# Rejestrator_WD.net
KiCad netlist of a schematic drawn in EAGLE
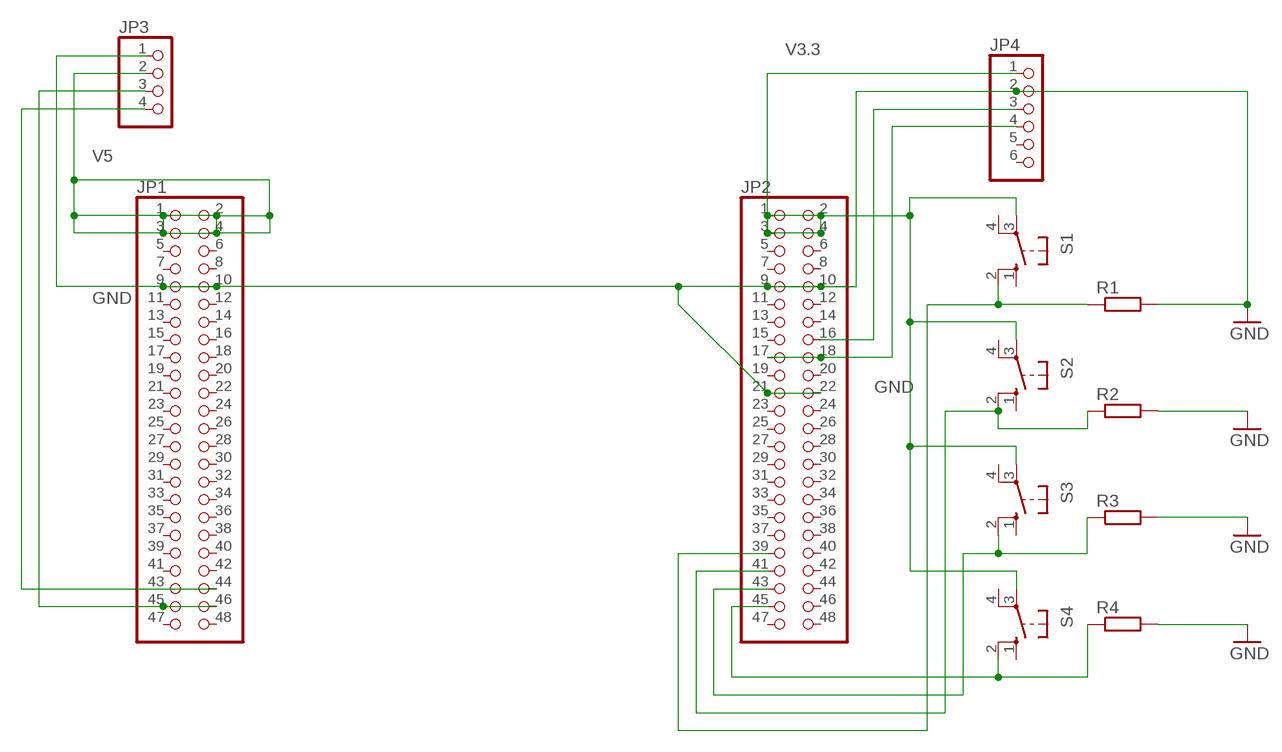
[diagram p0: schematic, sheet 1]

(export (version "E")
  (design (tool "Eeschema 10.0.6"))
  (components
    (comp (ref "JP1")
      (value "PINHD-2X24")
      (footprint "eagle-import:2X24")
      (libsource (lib "eagle-import") (part "PINHD-2X24"))
    )
    (comp (ref "JP2")
      (value "PINHD-2X24")
      (footprint "eagle-import:2X24")
      (libsource (lib "eagle-import") (part "PINHD-2X24"))
    )
    (comp (ref "JP3")
      (value "PINHD-1X4/90")
      (footprint "eagle-import:1X04_90")
      (libsource (lib "eagle-import") (part "PINHD-1X4/90"))
    )
    (comp (ref "JP4")
      (value "PINHD-1X6")
      (footprint "eagle-import:1X06")
      (libsource (lib "eagle-import") (part "PINHD-1X6"))
    )
    (comp (ref "R1")
      (value "R-EU_0207/10")
      (footprint "eagle-import:0207_10")
      (libsource (lib "eagle-import") (part "R-EU_0207/10"))
    )
    (comp (ref "R2")
      (value "R-EU_0207/10")
      (footprint "eagle-import:0207_10")
      (libsource (lib "eagle-import") (part "R-EU_0207/10"))
    )
    (comp (ref "R3")
      (value "R-EU_0207/10")
      (footprint "eagle-import:0207_10")
      (libsource (lib "eagle-import") (part "R-EU_0207/10"))
    )
    (comp (ref "R4")
      (value "R-EU_0207/10")
      (footprint "eagle-import:0207_10")
      (libsource (lib "eagle-import") (part "R-EU_0207/10"))
    )
    (comp (ref "S1")
      (value "40-XX")
      (footprint "eagle-import:B3F-40XX")
      (fields (field (name "MF") "OMRON COMPONENTS USA") (field (name "MPN") "B3F-4000"))
      (libsource (lib "eagle-import") (part "40-XX"))
    )
    (comp (ref "S2")
      (value "40-XX")
      (footprint "eagle-import:B3F-40XX")
      (fields (field (name "MF") "OMRON COMPONENTS USA") (field (name "MPN") "B3F-4000"))
      (libsource (lib "eagle-import") (part "40-XX"))
    )
    (comp (ref "S3")
      (value "40-XX")
      (footprint "eagle-import:B3F-40XX")
      (fields (field (name "MF") "OMRON COMPONENTS USA") (field (name "MPN") "B3F-4000"))
      (libsource (lib "eagle-import") (part "40-XX"))
    )
    (comp (ref "S4")
      (value "40-XX")
      (footprint "eagle-import:B3F-40XX")
      (fields (field (name "MF") "OMRON COMPONENTS USA") (field (name "MPN") "B3F-4000"))
      (libsource (lib "eagle-import") (part "40-XX"))
    )
  )
  (nets
    (net (code "1") (name "/V3.3") (class "Default")
      (node (ref "JP2") (pin "1") (pinfunction "1_1") (pintype "passive"))
      (node (ref "JP2") (pin "2") (pinfunction "2_2") (pintype "passive"))
      (node (ref "JP2") (pin "3") (pinfunction "3_3") (pintype "passive"))
      (node (ref "JP2") (pin "4") (pinfunction "4_4") (pintype "passive"))
      (node (ref "JP4") (pin "1") (pinfunction "1_1") (pintype "passive"))
      (node (ref "S1") (pin "3") (pinfunction "P_3") (pintype "passive"))
      (node (ref "S2") (pin "3") (pinfunction "P_3") (pintype "passive"))
      (node (ref "S3") (pin "3") (pinfunction "P_3") (pintype "passive"))
      (node (ref "S4") (pin "3") (pinfunction "P_3") (pintype "passive"))
    )
    (net (code "2") (name "/V5") (class "Default")
      (node (ref "JP1") (pin "1") (pinfunction "1_1") (pintype "passive"))
      (node (ref "JP1") (pin "2") (pinfunction "2_2") (pintype "passive"))
      (node (ref "JP1") (pin "3") (pinfunction "3_3") (pintype "passive"))
      (node (ref "JP1") (pin "4") (pinfunction "4_4") (pintype "passive"))
      (node (ref "JP3") (pin "2") (pinfunction "2_2") (pintype "passive"))
    )
    (net (code "3") (name "GND") (class "Default")
      (node (ref "JP1") (pin "10") (pinfunction "10_10") (pintype "passive"))
      (node (ref "JP1") (pin "9") (pinfunction "9_9") (pintype "passive"))
      (node (ref "JP2") (pin "10") (pinfunction "10_10") (pintype "passive"))
      (node (ref "JP2") (pin "21") (pinfunction "21_21") (pintype "passive"))
      (node (ref "JP2") (pin "22") (pinfunction "22_22") (pintype "passive"))
      (node (ref "JP2") (pin "9") (pinfunction "9_9") (pintype "passive"))
      (node (ref "JP3") (pin "1") (pinfunction "1_1") (pintype "passive"))
      (node (ref "JP4") (pin "2") (pinfunction "2_2") (pintype "passive"))
      (node (ref "R1") (pin "2") (pinfunction "2_2") (pintype "passive"))
      (node (ref "R2") (pin "2") (pinfunction "2_2") (pintype "passive"))
      (node (ref "R3") (pin "2") (pinfunction "2_2") (pintype "passive"))
      (node (ref "R4") (pin "2") (pinfunction "2_2") (pintype "passive"))
    )
    (net (code "4") (name "Net-(JP1-Pad44)") (class "Default")
      (node (ref "JP1") (pin "44") (pinfunction "44_44") (pintype "passive"))
      (node (ref "JP3") (pin "4") (pinfunction "4_4") (pintype "passive"))
    )
    (net (code "5") (name "Net-(JP1-Pad45)") (class "Default")
      (node (ref "JP1") (pin "45") (pinfunction "45_45") (pintype "passive"))
      (node (ref "JP1") (pin "46") (pinfunction "46_46") (pintype "passive"))
      (node (ref "JP3") (pin "3") (pinfunction "3_3") (pintype "passive"))
    )
    (net (code "6") (name "Net-(JP2-Pad16)") (class "Default")
      (node (ref "JP2") (pin "16") (pinfunction "16_16") (pintype "passive"))
      (node (ref "JP4") (pin "3") (pinfunction "3_3") (pintype "passive"))
    )
    (net (code "7") (name "Net-(JP2-Pad17)") (class "Default")
      (node (ref "JP2") (pin "17") (pinfunction "17_17") (pintype "passive"))
      (node (ref "JP2") (pin "18") (pinfunction "18_18") (pintype "passive"))
      (node (ref "JP4") (pin "4") (pinfunction "4_4") (pintype "passive"))
    )
    (net (code "8") (name "Net-(S1-S1)") (class "Default")
      (node (ref "JP2") (pin "39") (pinfunction "39_39") (pintype "passive"))
      (node (ref "R1") (pin "1") (pinfunction "1_1") (pintype "passive"))
      (node (ref "S1") (pin "2") (pinfunction "S1_2") (pintype "passive"))
    )
    (net (code "9") (name "Net-(S2-S1)") (class "Default")
      (node (ref "JP2") (pin "41") (pinfunction "41_41") (pintype "passive"))
      (node (ref "R2") (pin "1") (pinfunction "1_1") (pintype "passive"))
      (node (ref "S2") (pin "2") (pinfunction "S1_2") (pintype "passive"))
    )
    (net (code "10") (name "Net-(S3-S1)") (class "Default")
      (node (ref "JP2") (pin "43") (pinfunction "43_43") (pintype "passive"))
      (node (ref "R3") (pin "1") (pinfunction "1_1") (pintype "passive"))
      (node (ref "S3") (pin "2") (pinfunction "S1_2") (pintype "passive"))
    )
    (net (code "11") (name "Net-(S4-S1)") (class "Default")
      (node (ref "JP2") (pin "45") (pinfunction "45_45") (pintype "passive"))
      (node (ref "R4") (pin "1") (pinfunction "1_1") (pintype "passive"))
      (node (ref "S4") (pin "2") (pinfunction "S1_2") (pintype "passive"))
    )
    (net (code "12") (name "unconnected-(JP1-Pad5)") (class "Default")
      (node (ref "JP1") (pin "5") (pinfunction "5_5") (pintype "passive"))
    )
    (net (code "13") (name "unconnected-(JP1-Pad6)") (class "Default")
      (node (ref "JP1") (pin "6") (pinfunction "6_6") (pintype "passive"))
    )
    (net (code "14") (name "unconnected-(JP1-Pad7)") (class "Default")
      (node (ref "JP1") (pin "7") (pinfunction "7_7") (pintype "passive"))
    )
    (net (code "15") (name "unconnected-(JP1-Pad8)") (class "Default")
      (node (ref "JP1") (pin "8") (pinfunction "8_8") (pintype "passive"))
    )
    (net (code "16") (name "unconnected-(JP1-Pad11)") (class "Default")
      (node (ref "JP1") (pin "11") (pinfunction "11_11") (pintype "passive"))
    )
    (net (code "17") (name "unconnected-(JP1-Pad12)") (class "Default")
      (node (ref "JP1") (pin "12") (pinfunction "12_12") (pintype "passive"))
    )
    (net (code "18") (name "unconnected-(JP1-Pad13)") (class "Default")
      (node (ref "JP1") (pin "13") (pinfunction "13_13") (pintype "passive"))
    )
    (net (code "19") (name "unconnected-(JP1-Pad14)") (class "Default")
      (node (ref "JP1") (pin "14") (pinfunction "14_14") (pintype "passive"))
    )
    (net (code "20") (name "unconnected-(JP1-Pad15)") (class "Default")
      (node (ref "JP1") (pin "15") (pinfunction "15_15") (pintype "passive"))
    )
    (net (code "21") (name "unconnected-(JP1-Pad16)") (class "Default")
      (node (ref "JP1") (pin "16") (pinfunction "16_16") (pintype "passive"))
    )
    (net (code "22") (name "unconnected-(JP1-Pad17)") (class "Default")
      (node (ref "JP1") (pin "17") (pinfunction "17_17") (pintype "passive"))
    )
    (net (code "23") (name "unconnected-(JP1-Pad18)") (class "Default")
      (node (ref "JP1") (pin "18") (pinfunction "18_18") (pintype "passive"))
    )
    (net (code "24") (name "unconnected-(JP1-Pad19)") (class "Default")
      (node (ref "JP1") (pin "19") (pinfunction "19_19") (pintype "passive"))
    )
    (net (code "25") (name "unconnected-(JP1-Pad20)") (class "Default")
      (node (ref "JP1") (pin "20") (pinfunction "20_20") (pintype "passive"))
    )
    (net (code "26") (name "unconnected-(JP1-Pad21)") (class "Default")
      (node (ref "JP1") (pin "21") (pinfunction "21_21") (pintype "passive"))
    )
    (net (code "27") (name "unconnected-(JP1-Pad22)") (class "Default")
      (node (ref "JP1") (pin "22") (pinfunction "22_22") (pintype "passive"))
    )
    (net (code "28") (name "unconnected-(JP1-Pad23)") (class "Default")
      (node (ref "JP1") (pin "23") (pinfunction "23_23") (pintype "passive"))
    )
    (net (code "29") (name "unconnected-(JP1-Pad24)") (class "Default")
      (node (ref "JP1") (pin "24") (pinfunction "24_24") (pintype "passive"))
    )
    (net (code "30") (name "unconnected-(JP1-Pad25)") (class "Default")
      (node (ref "JP1") (pin "25") (pinfunction "25_25") (pintype "passive"))
    )
    (net (code "31") (name "unconnected-(JP1-Pad26)") (class "Default")
      (node (ref "JP1") (pin "26") (pinfunction "26_26") (pintype "passive"))
    )
    (net (code "32") (name "unconnected-(JP1-Pad27)") (class "Default")
      (node (ref "JP1") (pin "27") (pinfunction "27_27") (pintype "passive"))
    )
    (net (code "33") (name "unconnected-(JP1-Pad28)") (class "Default")
      (node (ref "JP1") (pin "28") (pinfunction "28_28") (pintype "passive"))
    )
    (net (code "34") (name "unconnected-(JP1-Pad29)") (class "Default")
      (node (ref "JP1") (pin "29") (pinfunction "29_29") (pintype "passive"))
    )
    (net (code "35") (name "unconnected-(JP1-Pad30)") (class "Default")
      (node (ref "JP1") (pin "30") (pinfunction "30_30") (pintype "passive"))
    )
    (net (code "36") (name "unconnected-(JP1-Pad31)") (class "Default")
      (node (ref "JP1") (pin "31") (pinfunction "31_31") (pintype "passive"))
    )
    (net (code "37") (name "unconnected-(JP1-Pad32)") (class "Default")
      (node (ref "JP1") (pin "32") (pinfunction "32_32") (pintype "passive"))
    )
    (net (code "38") (name "unconnected-(JP1-Pad33)") (class "Default")
      (node (ref "JP1") (pin "33") (pinfunction "33_33") (pintype "passive"))
    )
    (net (code "39") (name "unconnected-(JP1-Pad34)") (class "Default")
      (node (ref "JP1") (pin "34") (pinfunction "34_34") (pintype "passive"))
    )
    (net (code "40") (name "unconnected-(JP1-Pad35)") (class "Default")
      (node (ref "JP1") (pin "35") (pinfunction "35_35") (pintype "passive"))
    )
    (net (code "41") (name "unconnected-(JP1-Pad36)") (class "Default")
      (node (ref "JP1") (pin "36") (pinfunction "36_36") (pintype "passive"))
    )
    (net (code "42") (name "unconnected-(JP1-Pad37)") (class "Default")
      (node (ref "JP1") (pin "37") (pinfunction "37_37") (pintype "passive"))
    )
    (net (code "43") (name "unconnected-(JP1-Pad38)") (class "Default")
      (node (ref "JP1") (pin "38") (pinfunction "38_38") (pintype "passive"))
    )
    (net (code "44") (name "unconnected-(JP1-Pad39)") (class "Default")
      (node (ref "JP1") (pin "39") (pinfunction "39_39") (pintype "passive"))
    )
    (net (code "45") (name "unconnected-(JP1-Pad40)") (class "Default")
      (node (ref "JP1") (pin "40") (pinfunction "40_40") (pintype "passive"))
    )
    (net (code "46") (name "unconnected-(JP1-Pad41)") (class "Default")
      (node (ref "JP1") (pin "41") (pinfunction "41_41") (pintype "passive"))
    )
    (net (code "47") (name "unconnected-(JP1-Pad42)") (class "Default")
      (node (ref "JP1") (pin "42") (pinfunction "42_42") (pintype "passive"))
    )
    (net (code "48") (name "unconnected-(JP1-Pad43)") (class "Default")
      (node (ref "JP1") (pin "43") (pinfunction "43_43") (pintype "passive"))
    )
    (net (code "49") (name "unconnected-(JP1-Pad47)") (class "Default")
      (node (ref "JP1") (pin "47") (pinfunction "47_47") (pintype "passive"))
    )
    (net (code "50") (name "unconnected-(JP1-Pad48)") (class "Default")
      (node (ref "JP1") (pin "48") (pinfunction "48_48") (pintype "passive"))
    )
    (net (code "51") (name "unconnected-(JP2-Pad5)") (class "Default")
      (node (ref "JP2") (pin "5") (pinfunction "5_5") (pintype "passive"))
    )
    (net (code "52") (name "unconnected-(JP2-Pad6)") (class "Default")
      (node (ref "JP2") (pin "6") (pinfunction "6_6") (pintype "passive"))
    )
    (net (code "53") (name "unconnected-(JP2-Pad7)") (class "Default")
      (node (ref "JP2") (pin "7") (pinfunction "7_7") (pintype "passive"))
    )
    (net (code "54") (name "unconnected-(JP2-Pad8)") (class "Default")
      (node (ref "JP2") (pin "8") (pinfunction "8_8") (pintype "passive"))
    )
    (net (code "55") (name "unconnected-(JP2-Pad11)") (class "Default")
      (node (ref "JP2") (pin "11") (pinfunction "11_11") (pintype "passive"))
    )
    (net (code "56") (name "unconnected-(JP2-Pad12)") (class "Default")
      (node (ref "JP2") (pin "12") (pinfunction "12_12") (pintype "passive"))
    )
    (net (code "57") (name "unconnected-(JP2-Pad13)") (class "Default")
      (node (ref "JP2") (pin "13") (pinfunction "13_13") (pintype "passive"))
    )
    (net (code "58") (name "unconnected-(JP2-Pad14)") (class "Default")
      (node (ref "JP2") (pin "14") (pinfunction "14_14") (pintype "passive"))
    )
    (net (code "59") (name "unconnected-(JP2-Pad15)") (class "Default")
      (node (ref "JP2") (pin "15") (pinfunction "15_15") (pintype "passive"))
    )
    (net (code "60") (name "unconnected-(JP2-Pad19)") (class "Default")
      (node (ref "JP2") (pin "19") (pinfunction "19_19") (pintype "passive"))
    )
    (net (code "61") (name "unconnected-(JP2-Pad20)") (class "Default")
      (node (ref "JP2") (pin "20") (pinfunction "20_20") (pintype "passive"))
    )
    (net (code "62") (name "unconnected-(JP2-Pad23)") (class "Default")
      (node (ref "JP2") (pin "23") (pinfunction "23_23") (pintype "passive"))
    )
    (net (code "63") (name "unconnected-(JP2-Pad24)") (class "Default")
      (node (ref "JP2") (pin "24") (pinfunction "24_24") (pintype "passive"))
    )
    (net (code "64") (name "unconnected-(JP2-Pad25)") (class "Default")
      (node (ref "JP2") (pin "25") (pinfunction "25_25") (pintype "passive"))
    )
    (net (code "65") (name "unconnected-(JP2-Pad26)") (class "Default")
      (node (ref "JP2") (pin "26") (pinfunction "26_26") (pintype "passive"))
    )
    (net (code "66") (name "unconnected-(JP2-Pad27)") (class "Default")
      (node (ref "JP2") (pin "27") (pinfunction "27_27") (pintype "passive"))
    )
    (net (code "67") (name "unconnected-(JP2-Pad28)") (class "Default")
      (node (ref "JP2") (pin "28") (pinfunction "28_28") (pintype "passive"))
    )
    (net (code "68") (name "unconnected-(JP2-Pad29)") (class "Default")
      (node (ref "JP2") (pin "29") (pinfunction "29_29") (pintype "passive"))
    )
    (net (code "69") (name "unconnected-(JP2-Pad30)") (class "Default")
      (node (ref "JP2") (pin "30") (pinfunction "30_30") (pintype "passive"))
    )
    (net (code "70") (name "unconnected-(JP2-Pad31)") (class "Default")
      (node (ref "JP2") (pin "31") (pinfunction "31_31") (pintype "passive"))
    )
    (net (code "71") (name "unconnected-(JP2-Pad32)") (class "Default")
      (node (ref "JP2") (pin "32") (pinfunction "32_32") (pintype "passive"))
    )
    (net (code "72") (name "unconnected-(JP2-Pad33)") (class "Default")
      (node (ref "JP2") (pin "33") (pinfunction "33_33") (pintype "passive"))
    )
    (net (code "73") (name "unconnected-(JP2-Pad34)") (class "Default")
      (node (ref "JP2") (pin "34") (pinfunction "34_34") (pintype "passive"))
    )
    (net (code "74") (name "unconnected-(JP2-Pad35)") (class "Default")
      (node (ref "JP2") (pin "35") (pinfunction "35_35") (pintype "passive"))
    )
    (net (code "75") (name "unconnected-(JP2-Pad36)") (class "Default")
      (node (ref "JP2") (pin "36") (pinfunction "36_36") (pintype "passive"))
    )
    (net (code "76") (name "unconnected-(JP2-Pad37)") (class "Default")
      (node (ref "JP2") (pin "37") (pinfunction "37_37") (pintype "passive"))
    )
    (net (code "77") (name "unconnected-(JP2-Pad38)") (class "Default")
      (node (ref "JP2") (pin "38") (pinfunction "38_38") (pintype "passive"))
    )
    (net (code "78") (name "unconnected-(JP2-Pad40)") (class "Default")
      (node (ref "JP2") (pin "40") (pinfunction "40_40") (pintype "passive"))
    )
    (net (code "79") (name "unconnected-(JP2-Pad42)") (class "Default")
      (node (ref "JP2") (pin "42") (pinfunction "42_42") (pintype "passive"))
    )
    (net (code "80") (name "unconnected-(JP2-Pad44)") (class "Default")
      (node (ref "JP2") (pin "44") (pinfunction "44_44") (pintype "passive"))
    )
    (net (code "81") (name "unconnected-(JP2-Pad46)") (class "Default")
      (node (ref "JP2") (pin "46") (pinfunction "46_46") (pintype "passive"))
    )
    (net (code "82") (name "unconnected-(JP2-Pad47)") (class "Default")
      (node (ref "JP2") (pin "47") (pinfunction "47_47") (pintype "passive"))
    )
    (net (code "83") (name "unconnected-(JP2-Pad48)") (class "Default")
      (node (ref "JP2") (pin "48") (pinfunction "48_48") (pintype "passive"))
    )
    (net (code "84") (name "unconnected-(JP4-Pad5)") (class "Default")
      (node (ref "JP4") (pin "5") (pinfunction "5_5") (pintype "passive"))
    )
    (net (code "85") (name "unconnected-(JP4-Pad6)") (class "Default")
      (node (ref "JP4") (pin "6") (pinfunction "6_6") (pintype "passive"))
    )
    (net (code "86") (name "unconnected-(S1-P1-Pad4)") (class "Default")
      (node (ref "S1") (pin "4") (pinfunction "P1_4") (pintype "passive"))
    )
    (net (code "87") (name "unconnected-(S1-S-Pad1)") (class "Default")
      (node (ref "S1") (pin "1") (pinfunction "S_1") (pintype "passive"))
    )
    (net (code "88") (name "unconnected-(S2-P1-Pad4)") (class "Default")
      (node (ref "S2") (pin "4") (pinfunction "P1_4") (pintype "passive"))
    )
    (net (code "89") (name "unconnected-(S2-S-Pad1)") (class "Default")
      (node (ref "S2") (pin "1") (pinfunction "S_1") (pintype "passive"))
    )
    (net (code "90") (name "unconnected-(S3-P1-Pad4)") (class "Default")
      (node (ref "S3") (pin "4") (pinfunction "P1_4") (pintype "passive"))
    )
    (net (code "91") (name "unconnected-(S3-S-Pad1)") (class "Default")
      (node (ref "S3") (pin "1") (pinfunction "S_1") (pintype "passive"))
    )
    (net (code "92") (name "unconnected-(S4-P1-Pad4)") (class "Default")
      (node (ref "S4") (pin "4") (pinfunction "P1_4") (pintype "passive"))
    )
    (net (code "93") (name "unconnected-(S4-S-Pad1)") (class "Default")
      (node (ref "S4") (pin "1") (pinfunction "S_1") (pintype "passive"))
    )
  )
)
